# Sheet1.net
KiCad netlist of a schematic drawn in Altium Designer
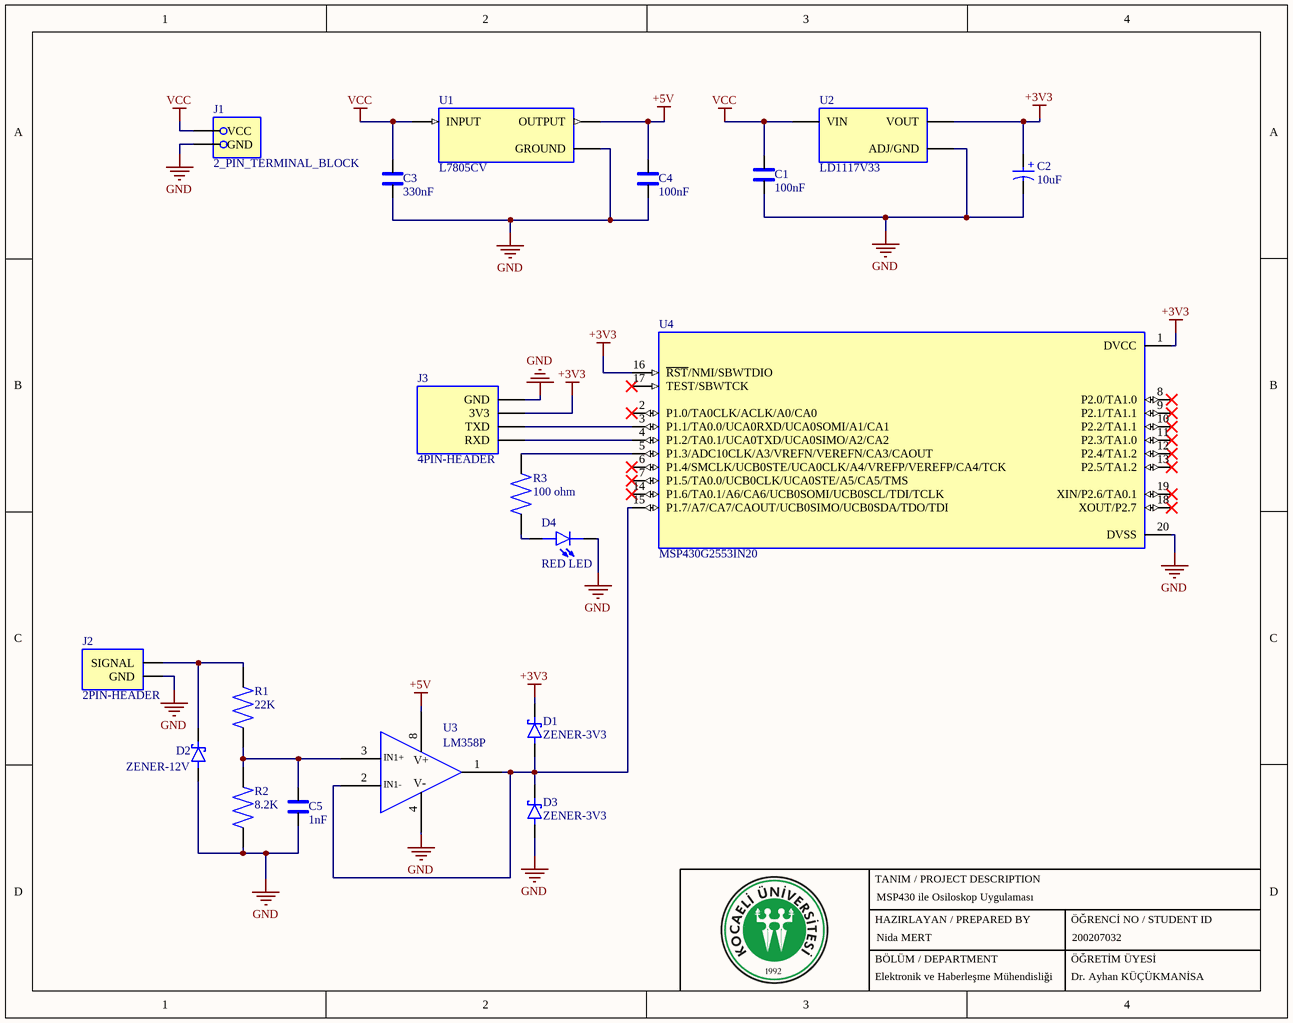
[diagram p0: Sheet1.SchDoc]

(export (version "E")
  (design (tool "Eeschema 10.0.6"))
  (components
    (comp (ref "C1")
      (value "100nF")
      (footprint "5MM-CAPACITOR-UNIPOLAR")
      (libsource (lib "Schlib1") (part "Capacitor-Unipolar"))
    )
    (comp (ref "C2")
      (value "10uF")
      (footprint "5mm_Capacitor")
      (libsource (lib "Schlib1") (part "Capacitor"))
    )
    (comp (ref "C3")
      (value "330nF")
      (footprint "5MM-CAPACITOR-UNIPOLAR")
      (libsource (lib "Schlib1") (part "Capacitor-Unipolar"))
    )
    (comp (ref "C4")
      (value "100nF")
      (footprint "5MM-CAPACITOR-UNIPOLAR")
      (libsource (lib "Schlib1") (part "Capacitor-Unipolar"))
    )
    (comp (ref "C5")
      (value "1nF")
      (footprint "5MM-CAPACITOR-UNIPOLAR")
      (libsource (lib "Schlib1") (part "Capacitor-Unipolar"))
    )
    (comp (ref "D1") (value "ZENER-3V3") (footprint "ZENER") (libsource (lib "Schlib1") (part "ZENER")))
    (comp (ref "D2") (value "ZENER-12V") (footprint "ZENER") (libsource (lib "Schlib1") (part "ZENER")))
    (comp (ref "D3") (value "ZENER-3V3") (footprint "ZENER") (libsource (lib "Schlib1") (part "ZENER")))
    (comp (ref "D4") (value "RED LED") (footprint "LED") (libsource (lib "Schlib1") (part "LED")))
    (comp (ref "J1")
      (value "2_PIN_TERMINAL_BLOCK")
      (footprint "2_PIN_TERMINAL_BLOCK")
      (libsource (lib "Schlib1") (part "2_PIN_TERMINAL_BLOCK"))
    )
    (comp (ref "J2")
      (value "2PIN-HEADER")
      (footprint "2PIN-HEADER-2.54mm")
      (libsource (lib "Schlib1") (part "2PIN-HEADER"))
    )
    (comp (ref "J3")
      (value "4PIN-HEADER")
      (footprint "4PIN-HEADER-2.54mm")
      (libsource (lib "Schlib1") (part "4PIN-HEADER"))
    )
    (comp (ref "R1") (value "22K") (footprint "7MM_RESISTOR") (libsource (lib "Schlib1") (part "Resistor")))
    (comp (ref "R2") (value "8.2K") (footprint "7MM_RESISTOR") (libsource (lib "Schlib1") (part "Resistor")))
    (comp (ref "R3")
      (value "100 ohm")
      (footprint "7MM_RESISTOR")
      (libsource (lib "Schlib1") (part "Resistor"))
    )
    (comp (ref "U1")
      (value "L7805CV")
      (footprint "L7805CV_TO220")
      (libsource (lib "Schlib1") (part "L7805CV"))
    )
    (comp (ref "U2")
      (value "LD1117V33")
      (footprint "LD1117_TO-220AB")
      (libsource (lib "Schlib1") (part "LD1117V33"))
    )
    (comp (ref "U3") (value "LM358P") (footprint "LM358P") (libsource (lib "Schlib1") (part "LM358P")))
    (comp (ref "U4")
      (value "MSP430G2553IN20")
      (footprint "DIP20-TH")
      (libsource (lib "Schlib1") (part "MSP430G2553IN20"))
    )
  )
  (nets
    (net (code "1") (name "+3V3") (class "Default")
      (node (ref "C2") (pin "1") (pinfunction "P_1") (pintype "passive"))
      (node (ref "D1") (pin "1") (pinfunction "K_1") (pintype "passive"))
      (node (ref "J3") (pin "02") (pinfunction "3V3_02") (pintype "passive"))
      (node (ref "U2") (pin "2") (pinfunction "VOUT_2") (pintype "passive"))
      (node (ref "U4") (pin "1") (pinfunction "DVCC_1") (pintype "power_in"))
      (node (ref "U4") (pin "16") (pinfunction "~{RST}/NMI/SBWTDIO_16") (pintype "input"))
    )
    (net (code "2") (name "+5V") (class "Default")
      (node (ref "C4") (pin "2") (pinfunction "2_2") (pintype "passive"))
      (node (ref "U1") (pin "3") (pinfunction "OUTPUT_3") (pintype "output"))
      (node (ref "U3") (pin "8") (pinfunction "8_8") (pintype "passive"))
    )
    (net (code "3") (name "GND") (class "Default")
      (node (ref "C1") (pin "1") (pinfunction "1_1") (pintype "passive"))
      (node (ref "C2") (pin "2") (pinfunction "N_2") (pintype "passive"))
      (node (ref "C3") (pin "1") (pinfunction "1_1") (pintype "passive"))
      (node (ref "C4") (pin "1") (pinfunction "1_1") (pintype "passive"))
      (node (ref "C5") (pin "1") (pinfunction "1_1") (pintype "passive"))
      (node (ref "D2") (pin "2") (pinfunction "A_2") (pintype "passive"))
      (node (ref "D3") (pin "2") (pinfunction "A_2") (pintype "passive"))
      (node (ref "D4") (pin "C") (pinfunction "C_C") (pintype "passive"))
      (node (ref "J1") (pin "2") (pinfunction "GND_2") (pintype "passive"))
      (node (ref "J2") (pin "2") (pinfunction "GND_2") (pintype "passive"))
      (node (ref "J3") (pin "01") (pinfunction "GND_01") (pintype "passive"))
      (node (ref "R2") (pin "1") (pinfunction "1_1") (pintype "passive"))
      (node (ref "U1") (pin "2") (pinfunction "GROUND_2") (pintype "power_in"))
      (node (ref "U2") (pin "1") (pinfunction "ADJ/GND_1") (pintype "passive"))
      (node (ref "U3") (pin "4") (pinfunction "4_4") (pintype "passive"))
      (node (ref "U4") (pin "20") (pinfunction "DVSS_20") (pintype "power_in"))
    )
    (net (code "4") (name "Net-(C5-Pad2)") (class "Default")
      (node (ref "C5") (pin "2") (pinfunction "2_2") (pintype "passive"))
      (node (ref "R1") (pin "1") (pinfunction "1_1") (pintype "passive"))
      (node (ref "R2") (pin "2") (pinfunction "2_2") (pintype "passive"))
      (node (ref "U3") (pin "3") (pinfunction "3_3") (pintype "passive"))
    )
    (net (code "5") (name "Net-(D1-A)") (class "Default")
      (node (ref "D1") (pin "2") (pinfunction "A_2") (pintype "passive"))
      (node (ref "D3") (pin "1") (pinfunction "K_1") (pintype "passive"))
      (node (ref "U3") (pin "1") (pinfunction "1_1") (pintype "passive"))
      (node (ref "U3") (pin "2") (pinfunction "2_2") (pintype "passive"))
      (node (ref "U4") (pin "15") (pinfunction "P1.7/A7/CA7/CAOUT/UCB0SIMO/UCB0SDA/TDO/TDI_15") (pintype "bidirectional"))
    )
    (net (code "6") (name "Net-(D2-K)") (class "Default")
      (node (ref "D2") (pin "1") (pinfunction "K_1") (pintype "passive"))
      (node (ref "J2") (pin "1") (pinfunction "SIGNAL_1") (pintype "passive"))
      (node (ref "R1") (pin "2") (pinfunction "2_2") (pintype "passive"))
    )
    (net (code "7") (name "Net-(D4-PadA)") (class "Default")
      (node (ref "D4") (pin "A") (pinfunction "A_A") (pintype "passive"))
      (node (ref "R3") (pin "1") (pinfunction "1_1") (pintype "passive"))
    )
    (net (code "8") (name "Net-(J3-RXD)") (class "Default")
      (node (ref "J3") (pin "04") (pinfunction "RXD_04") (pintype "passive"))
      (node (ref "U4") (pin "4") (pinfunction "P1.2/TA0.1/UCA0TXD/UCA0SIMO/A2/CA2_4") (pintype "bidirectional"))
    )
    (net (code "9") (name "Net-(J3-TXD)") (class "Default")
      (node (ref "J3") (pin "03") (pinfunction "TXD_03") (pintype "passive"))
      (node (ref "U4") (pin "3") (pinfunction "P1.1/TA0.0/UCA0RXD/UCA0SOMI/A1/CA1_3") (pintype "bidirectional"))
    )
    (net (code "10") (name "Net-(U4-P1.3{slash}ADC10CLK{slash}A3{slash}VREFN{slash}VEREFN{slash}CA3{slash}CAOUT)") (class "Default")
      (node (ref "R3") (pin "2") (pinfunction "2_2") (pintype "passive"))
      (node (ref "U4") (pin "5") (pinfunction "P1.3/ADC10CLK/A3/VREFN/VEREFN/CA3/CAOUT_5") (pintype "bidirectional"))
    )
    (net (code "11") (name "VCC") (class "Default")
      (node (ref "C1") (pin "2") (pinfunction "2_2") (pintype "passive"))
      (node (ref "C3") (pin "2") (pinfunction "2_2") (pintype "passive"))
      (node (ref "J1") (pin "1") (pinfunction "VCC_1") (pintype "passive"))
      (node (ref "U1") (pin "1") (pinfunction "INPUT_1") (pintype "input"))
      (node (ref "U2") (pin "3") (pinfunction "VIN_3") (pintype "passive"))
    )
    (net (code "12") (name "unconnected-(U4-P1.0{slash}TA0CLK{slash}ACLK{slash}A0{slash}CA0-Pad2)") (class "Default")
      (node (ref "U4") (pin "2") (pinfunction "P1.0/TA0CLK/ACLK/A0/CA0_2") (pintype "bidirectional+no_connect"))
    )
    (net (code "13") (name "unconnected-(U4-P1.4{slash}SMCLK{slash}UCB0STE{slash}UCA0CLK{slash}A4{slash}VREFP{slash}VEREFP{slash}CA4{slash}TCK-Pad6)") (class "Default")
      (node (ref "U4") (pin "6") (pinfunction "P1.4/SMCLK/UCB0STE/UCA0CLK/A4/VREFP/VEREFP/CA4/TCK_6") (pintype "bidirectional+no_connect"))
    )
    (net (code "14") (name "unconnected-(U4-P1.5{slash}TA0.0{slash}UCB0CLK{slash}UCA0STE{slash}A5{slash}CA5{slash}TMS-Pad7)") (class "Default")
      (node (ref "U4") (pin "7") (pinfunction "P1.5/TA0.0/UCB0CLK/UCA0STE/A5/CA5/TMS_7") (pintype "bidirectional+no_connect"))
    )
    (net (code "15") (name "unconnected-(U4-P1.6{slash}TA0.1{slash}A6{slash}CA6{slash}UCB0SOMI{slash}UCB0SCL{slash}TDI{slash}TCLK-Pad14)") (class "Default")
      (node (ref "U4") (pin "14") (pinfunction "P1.6/TA0.1/A6/CA6/UCB0SOMI/UCB0SCL/TDI/TCLK_14") (pintype "bidirectional+no_connect"))
    )
    (net (code "16") (name "unconnected-(U4-P2.0{slash}TA1.0-Pad8)") (class "Default")
      (node (ref "U4") (pin "8") (pinfunction "P2.0/TA1.0_8") (pintype "bidirectional+no_connect"))
    )
    (net (code "17") (name "unconnected-(U4-P2.1{slash}TA1.1-Pad9)") (class "Default")
      (node (ref "U4") (pin "9") (pinfunction "P2.1/TA1.1_9") (pintype "bidirectional+no_connect"))
    )
    (net (code "18") (name "unconnected-(U4-P2.2{slash}TA1.1-Pad10)") (class "Default")
      (node (ref "U4") (pin "10") (pinfunction "P2.2/TA1.1_10") (pintype "bidirectional+no_connect"))
    )
    (net (code "19") (name "unconnected-(U4-P2.3{slash}TA1.0-Pad11)") (class "Default")
      (node (ref "U4") (pin "11") (pinfunction "P2.3/TA1.0_11") (pintype "bidirectional+no_connect"))
    )
    (net (code "20") (name "unconnected-(U4-P2.4{slash}TA1.2-Pad12)") (class "Default")
      (node (ref "U4") (pin "12") (pinfunction "P2.4/TA1.2_12") (pintype "bidirectional+no_connect"))
    )
    (net (code "21") (name "unconnected-(U4-P2.5{slash}TA1.2-Pad13)") (class "Default")
      (node (ref "U4") (pin "13") (pinfunction "P2.5/TA1.2_13") (pintype "bidirectional+no_connect"))
    )
    (net (code "22") (name "unconnected-(U4-TEST{slash}SBWTCK-Pad17)") (class "Default")
      (node (ref "U4") (pin "17") (pinfunction "TEST/SBWTCK_17") (pintype "input+no_connect"))
    )
    (net (code "23") (name "unconnected-(U4-XIN{slash}P2.6{slash}TA0.1-Pad19)") (class "Default")
      (node (ref "U4") (pin "19") (pinfunction "XIN/P2.6/TA0.1_19") (pintype "bidirectional+no_connect"))
    )
    (net (code "24") (name "unconnected-(U4-XOUT{slash}P2.7-Pad18)") (class "Default")
      (node (ref "U4") (pin "18") (pinfunction "XOUT/P2.7_18") (pintype "bidirectional+no_connect"))
    )
  )
)
